# iso1212_inputs.net
KiCad netlist of a schematic drawn in Altium Designer
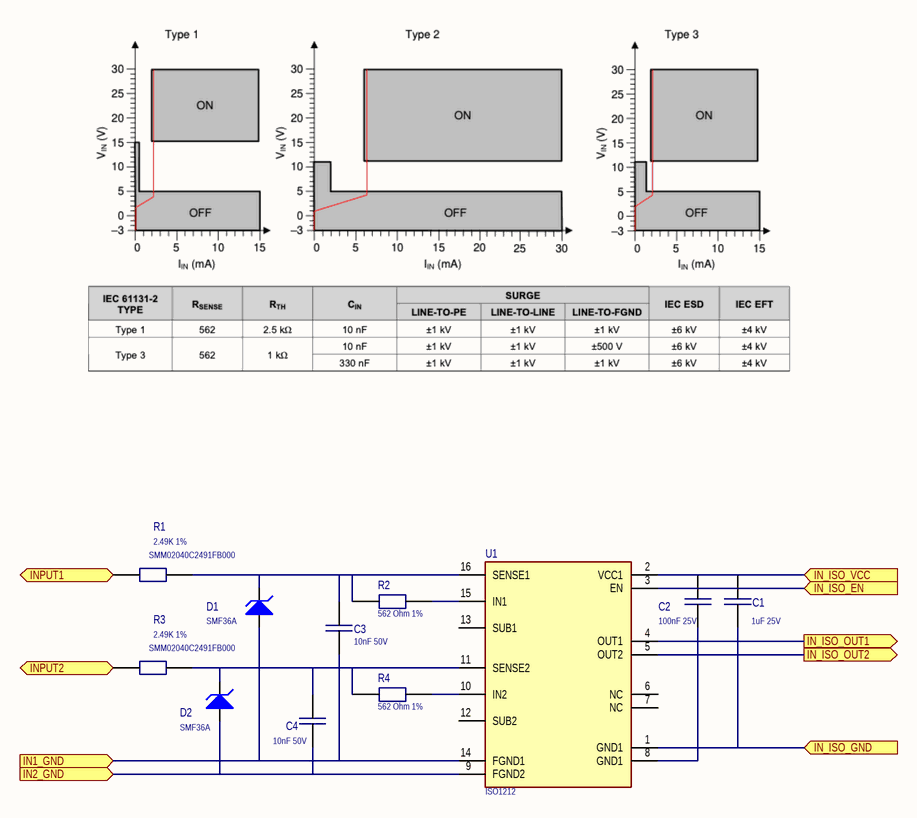
[diagram p0: iso1212_inputs.schdoc]

(export (version "E")
  (design (tool "Eeschema 10.0.6"))
  (components
    (comp (ref "C1")
      (value "1uF 25V")
      (footprint "C_0603")
      (description "Capacitor")
      (libsource (lib "capacitors") (part "C0603"))
    )
    (comp (ref "C2")
      (value "100nF 25V")
      (footprint "C_0603")
      (description "Capacitor")
      (libsource (lib "capacitors") (part "C0603"))
    )
    (comp (ref "C3")
      (value "10nF 50V")
      (footprint "C_0603")
      (description "Capacitor")
      (libsource (lib "capacitors") (part "C0603"))
    )
    (comp (ref "C4")
      (value "10nF 50V")
      (footprint "C_0603")
      (description "Capacitor")
      (libsource (lib "capacitors") (part "C0603"))
    )
    (comp (ref "D1") (value "SMF36A") (footprint "SOD123FL") (libsource (lib "diode") (part "D_SOD123FL")))
    (comp (ref "D2") (value "SMF36A") (footprint "SOD123FL") (libsource (lib "diode") (part "D_SOD123FL")))
    (comp (ref "R1")
      (value "SMM02040C2491FB000")
      (footprint "FP-SMM0204-IPC_C")
      (description "Resistor")
      (fields (field (name "ALTIUM_VALUE") "2.49K 1%"))
      (libsource (lib "resistors") (part "SMM0204"))
    )
    (comp (ref "R2")
      (value "562 Ohm 1%")
      (footprint "R_0603")
      (description "Resistor")
      (libsource (lib "resistors") (part "R0603"))
    )
    (comp (ref "R3")
      (value "SMM02040C2491FB000")
      (footprint "FP-SMM0204-IPC_C")
      (description "Resistor")
      (fields (field (name "ALTIUM_VALUE") "2.49K 1%"))
      (libsource (lib "resistors") (part "SMM0204"))
    )
    (comp (ref "R4")
      (value "562 Ohm 1%")
      (footprint "R_0603")
      (description "Resistor")
      (libsource (lib "resistors") (part "R0603"))
    )
    (comp (ref "U1")
      (value "ISO1212")
      (footprint "FP-DBQ0016A-IPC_C")
      (libsource (lib "analog_ic") (part "ISO1212"))
    )
  )
  (nets
    (net (code "1") (name "/IN1_GND") (class "Default")
      (node (ref "C3") (pin "2") (pinfunction "2_2") (pintype "passive"))
      (node (ref "D1") (pin "1") (pinfunction "A_1") (pintype "passive"))
      (node (ref "U1") (pin "14") (pinfunction "FGND1_14") (pintype "passive"))
    )
    (net (code "2") (name "/IN2_GND") (class "Default")
      (node (ref "C4") (pin "2") (pinfunction "2_2") (pintype "passive"))
      (node (ref "D2") (pin "1") (pinfunction "A_1") (pintype "passive"))
      (node (ref "U1") (pin "9") (pinfunction "FGND2_9") (pintype "passive"))
    )
    (net (code "3") (name "/INPUT1") (class "Default")
      (node (ref "R1") (pin "1") (pinfunction "1_1") (pintype "passive"))
    )
    (net (code "4") (name "/INPUT2") (class "Default")
      (node (ref "R3") (pin "1") (pinfunction "1_1") (pintype "passive"))
    )
    (net (code "5") (name "/IN_ISO_EN") (class "Default")
      (node (ref "U1") (pin "3") (pinfunction "EN_3") (pintype "passive"))
    )
    (net (code "6") (name "/IN_ISO_GND") (class "Default")
      (node (ref "C1") (pin "1") (pinfunction "1_1") (pintype "passive"))
      (node (ref "C2") (pin "1") (pinfunction "1_1") (pintype "passive"))
      (node (ref "U1") (pin "1") (pinfunction "GND1_1") (pintype "passive"))
      (node (ref "U1") (pin "8") (pinfunction "GND1_8") (pintype "passive"))
    )
    (net (code "7") (name "/IN_ISO_OUT1") (class "Default")
      (node (ref "U1") (pin "4") (pinfunction "OUT1_4") (pintype "passive"))
    )
    (net (code "8") (name "/IN_ISO_OUT2") (class "Default")
      (node (ref "U1") (pin "5") (pinfunction "OUT2_5") (pintype "passive"))
    )
    (net (code "9") (name "/IN_ISO_VCC") (class "Default")
      (node (ref "C1") (pin "2") (pinfunction "2_2") (pintype "passive"))
      (node (ref "C2") (pin "2") (pinfunction "2_2") (pintype "passive"))
      (node (ref "U1") (pin "2") (pinfunction "VCC1_2") (pintype "passive"))
    )
    (net (code "10") (name "Net-(D1-K)") (class "Default")
      (node (ref "C3") (pin "1") (pinfunction "1_1") (pintype "passive"))
      (node (ref "D1") (pin "2") (pinfunction "K_2") (pintype "passive"))
      (node (ref "R1") (pin "2") (pinfunction "2_2") (pintype "passive"))
      (node (ref "R2") (pin "1") (pinfunction "1_1") (pintype "passive"))
      (node (ref "U1") (pin "16") (pinfunction "SENSE1_16") (pintype "passive"))
    )
    (net (code "11") (name "Net-(D2-K)") (class "Default")
      (node (ref "C4") (pin "1") (pinfunction "1_1") (pintype "passive"))
      (node (ref "D2") (pin "2") (pinfunction "K_2") (pintype "passive"))
      (node (ref "R3") (pin "2") (pinfunction "2_2") (pintype "passive"))
      (node (ref "R4") (pin "1") (pinfunction "1_1") (pintype "passive"))
      (node (ref "U1") (pin "11") (pinfunction "SENSE2_11") (pintype "passive"))
    )
    (net (code "12") (name "Net-(U1-IN1)") (class "Default")
      (node (ref "R2") (pin "2") (pinfunction "2_2") (pintype "passive"))
      (node (ref "U1") (pin "15") (pinfunction "IN1_15") (pintype "passive"))
    )
    (net (code "13") (name "Net-(U1-IN2)") (class "Default")
      (node (ref "R4") (pin "2") (pinfunction "2_2") (pintype "passive"))
      (node (ref "U1") (pin "10") (pinfunction "IN2_10") (pintype "passive"))
    )
    (net (code "14") (name "unconnected-(U1-NC-Pad6)") (class "Default")
      (node (ref "U1") (pin "6") (pinfunction "NC_6") (pintype "passive"))
    )
    (net (code "15") (name "unconnected-(U1-NC-Pad7)") (class "Default")
      (node (ref "U1") (pin "7") (pinfunction "NC_7") (pintype "passive"))
    )
    (net (code "16") (name "unconnected-(U1-SUB1-Pad13)") (class "Default")
      (node (ref "U1") (pin "13") (pinfunction "SUB1_13") (pintype "passive"))
    )
    (net (code "17") (name "unconnected-(U1-SUB2-Pad12)") (class "Default")
      (node (ref "U1") (pin "12") (pinfunction "SUB2_12") (pintype "passive"))
    )
  )
)
